# APRS_Interface.net
KiCad netlist of a schematic drawn in EAGLE
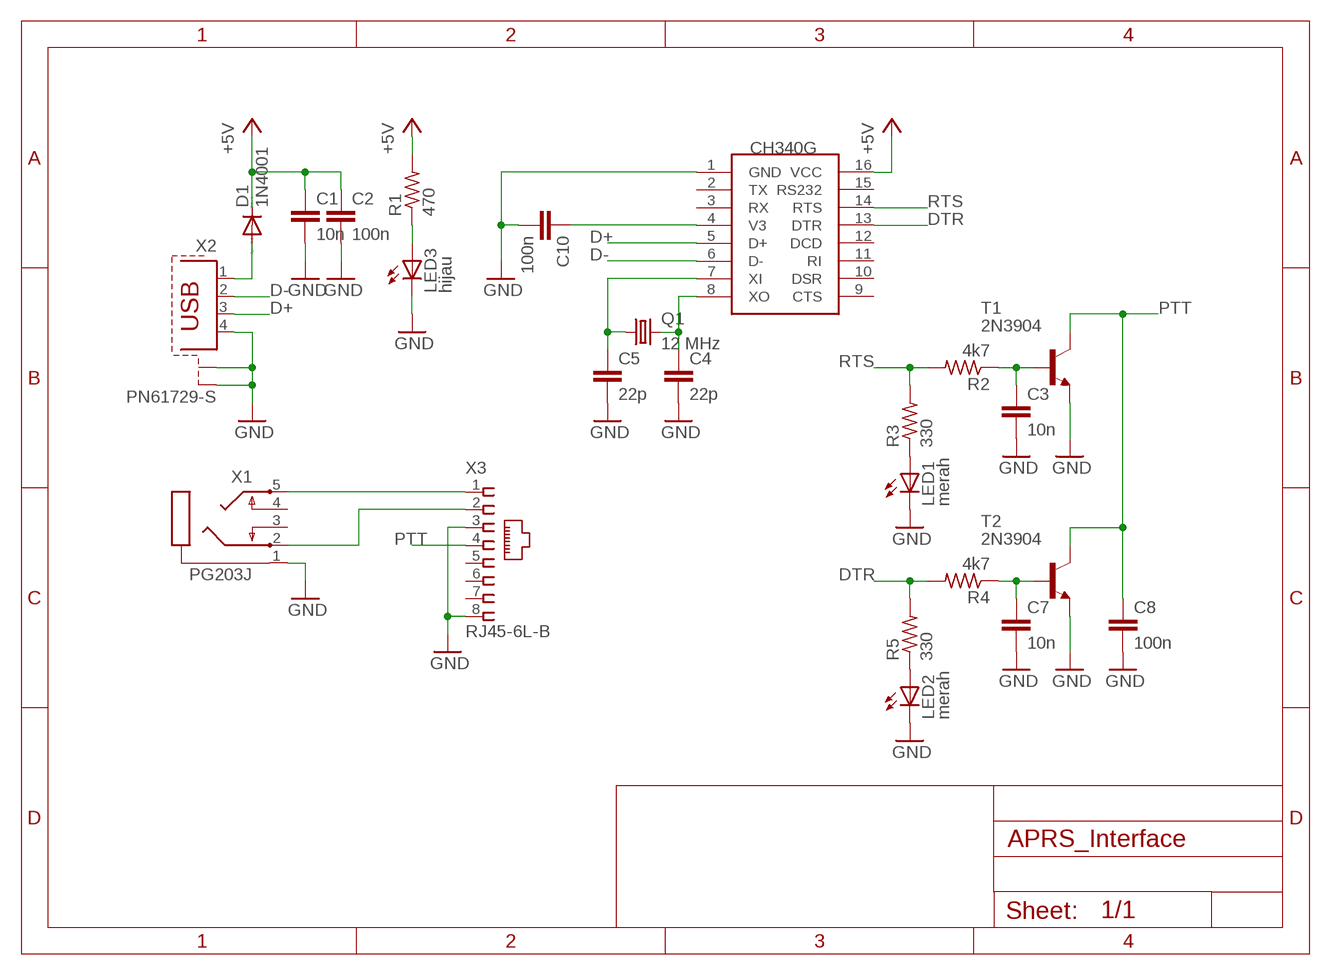
[diagram p0: schematic, sheet 1]

(export (version "E")
  (design (tool "Eeschema 10.0.6"))
  (components
    (comp (ref "C1")
      (value "10n")
      (footprint "eagle-import:C0805K")
      (libsource (lib "eagle-import") (part "C-EUC0805K"))
    )
    (comp (ref "C2")
      (value "100n")
      (footprint "eagle-import:C0805K")
      (libsource (lib "eagle-import") (part "C-EUC0805K"))
    )
    (comp (ref "C3")
      (value "10n")
      (footprint "eagle-import:C0805K")
      (libsource (lib "eagle-import") (part "C-EUC0805K"))
    )
    (comp (ref "C4")
      (value "22p")
      (footprint "eagle-import:C0805K")
      (libsource (lib "eagle-import") (part "C-EUC0805K"))
    )
    (comp (ref "C5")
      (value "22p")
      (footprint "eagle-import:C0805K")
      (libsource (lib "eagle-import") (part "C-EUC0805K"))
    )
    (comp (ref "C7")
      (value "10n")
      (footprint "eagle-import:C0805K")
      (libsource (lib "eagle-import") (part "C-EUC0805K"))
    )
    (comp (ref "C8")
      (value "100n")
      (footprint "eagle-import:C0805K")
      (libsource (lib "eagle-import") (part "C-EUC0805K"))
    )
    (comp (ref "C10")
      (value "100n")
      (footprint "eagle-import:C0805K")
      (libsource (lib "eagle-import") (part "C-EUC0805K"))
    )
    (comp (ref "D1")
      (value "1N4001")
      (footprint "eagle-import:DO35-7")
      (libsource (lib "eagle-import") (part "1N4148DO35-7"))
    )
    (comp (ref "LED1")
      (value "merah")
      (footprint "eagle-import:LED3MM")
      (libsource (lib "eagle-import") (part "LED3MM"))
    )
    (comp (ref "LED2")
      (value "merah")
      (footprint "eagle-import:LED3MM")
      (libsource (lib "eagle-import") (part "LED3MM"))
    )
    (comp (ref "LED3")
      (value "hijau")
      (footprint "eagle-import:LED3MM")
      (libsource (lib "eagle-import") (part "LED3MM"))
    )
    (comp (ref "Q1")
      (value "12 MHz")
      (footprint "eagle-import:HC49_S")
      (libsource (lib "eagle-import") (part "CRYSTALHC49S"))
    )
    (comp (ref "R1")
      (value "470")
      (footprint "eagle-import:R0805")
      (libsource (lib "eagle-import") (part "R-US_R0805"))
    )
    (comp (ref "R2")
      (value "4k7")
      (footprint "eagle-import:R0805")
      (libsource (lib "eagle-import") (part "R-US_R0805"))
    )
    (comp (ref "R3")
      (value "330")
      (footprint "eagle-import:R0805")
      (libsource (lib "eagle-import") (part "R-US_R0805"))
    )
    (comp (ref "R4")
      (value "4k7")
      (footprint "eagle-import:R0805")
      (libsource (lib "eagle-import") (part "R-US_R0805"))
    )
    (comp (ref "R5")
      (value "330")
      (footprint "eagle-import:R0805")
      (libsource (lib "eagle-import") (part "R-US_R0805"))
    )
    (comp (ref "T1")
      (value "2N3904")
      (footprint "eagle-import:TO92-EBC")
      (libsource (lib "eagle-import") (part "-NPN-TO92-EBC2N3904"))
    )
    (comp (ref "T2")
      (value "2N3904")
      (footprint "eagle-import:TO92-EBC")
      (libsource (lib "eagle-import") (part "-NPN-TO92-EBC2N3904"))
    )
    (comp (ref "U$1")
      (value "CH340G")
      (footprint "eagle-import:SOIC16")
      (libsource (lib "eagle-import") (part "CH340G"))
    )
    (comp (ref "X1")
      (value "PG203J")
      (footprint "eagle-import:PG203J")
      (libsource (lib "eagle-import") (part "PG203J"))
    )
    (comp (ref "X2")
      (value "PN61729-S")
      (footprint "eagle-import:PN61729-S")
      (libsource (lib "eagle-import") (part "PN61729-S"))
    )
    (comp (ref "X3")
      (value "RJ45-6L-B")
      (footprint "eagle-import:RJ45-NO-SHIELD")
      (libsource (lib "eagle-import") (part "RJ45-6L-B"))
    )
  )
  (nets
    (net (code "1") (name "+5V") (class "Default")
      (node (ref "C1") (pin "1") (pinfunction "1_1") (pintype "passive"))
      (node (ref "C2") (pin "1") (pinfunction "1_1") (pintype "passive"))
      (node (ref "D1") (pin "C") (pinfunction "C_C") (pintype "passive"))
      (node (ref "R1") (pin "2") (pinfunction "2_2") (pintype "passive"))
      (node (ref "U$1") (pin "16") (pinfunction "VCC_16") (pintype "bidirectional"))
    )
    (net (code "2") (name "/D+") (class "Default")
      (node (ref "U$1") (pin "5") (pinfunction "D+_5") (pintype "bidirectional"))
      (node (ref "X2") (pin "3") (pinfunction "3_3") (pintype "passive"))
    )
    (net (code "3") (name "/D-") (class "Default")
      (node (ref "U$1") (pin "6") (pinfunction "D-_6") (pintype "bidirectional"))
      (node (ref "X2") (pin "2") (pinfunction "2_2") (pintype "passive"))
    )
    (net (code "4") (name "/DTR") (class "Default")
      (node (ref "R4") (pin "2") (pinfunction "2_2") (pintype "passive"))
      (node (ref "R5") (pin "2") (pinfunction "2_2") (pintype "passive"))
      (node (ref "U$1") (pin "13") (pinfunction "DTR_13") (pintype "bidirectional"))
    )
    (net (code "5") (name "/PTT") (class "Default")
      (node (ref "C8") (pin "1") (pinfunction "1_1") (pintype "passive"))
      (node (ref "T1") (pin "C") (pinfunction "C_C") (pintype "passive"))
      (node (ref "T2") (pin "C") (pinfunction "C_C") (pintype "passive"))
      (node (ref "X3") (pin "4") (pinfunction "4_4") (pintype "passive"))
    )
    (net (code "6") (name "/RTS") (class "Default")
      (node (ref "R2") (pin "2") (pinfunction "2_2") (pintype "passive"))
      (node (ref "R3") (pin "2") (pinfunction "2_2") (pintype "passive"))
      (node (ref "U$1") (pin "14") (pinfunction "RTS_14") (pintype "bidirectional"))
    )
    (net (code "7") (name "GND") (class "Default")
      (node (ref "C1") (pin "2") (pinfunction "2_2") (pintype "passive"))
      (node (ref "C10") (pin "2") (pinfunction "2_2") (pintype "passive"))
      (node (ref "C2") (pin "2") (pinfunction "2_2") (pintype "passive"))
      (node (ref "C3") (pin "2") (pinfunction "2_2") (pintype "passive"))
      (node (ref "C4") (pin "2") (pinfunction "2_2") (pintype "passive"))
      (node (ref "C5") (pin "2") (pinfunction "2_2") (pintype "passive"))
      (node (ref "C7") (pin "2") (pinfunction "2_2") (pintype "passive"))
      (node (ref "C8") (pin "2") (pinfunction "2_2") (pintype "passive"))
      (node (ref "LED1") (pin "K") (pinfunction "C_K") (pintype "passive"))
      (node (ref "LED2") (pin "K") (pinfunction "C_K") (pintype "passive"))
      (node (ref "LED3") (pin "K") (pinfunction "C_K") (pintype "passive"))
      (node (ref "T1") (pin "E") (pinfunction "E_E") (pintype "passive"))
      (node (ref "T2") (pin "E") (pinfunction "E_E") (pintype "passive"))
      (node (ref "U$1") (pin "1") (pinfunction "GND_1") (pintype "bidirectional"))
      (node (ref "X1") (pin "1") (pinfunction "1_1") (pintype "passive"))
      (node (ref "X2") (pin "4") (pinfunction "4_4") (pintype "passive"))
      (node (ref "X2") (pin "S1") (pinfunction "S1_S1") (pintype "passive"))
      (node (ref "X2") (pin "S2") (pinfunction "S2_S2") (pintype "passive"))
      (node (ref "X3") (pin "3") (pinfunction "3_3") (pintype "passive"))
      (node (ref "X3") (pin "8") (pinfunction "8_8") (pintype "passive"))
    )
    (net (code "8") (name "Net-(C3-Pad1)") (class "Default")
      (node (ref "C3") (pin "1") (pinfunction "1_1") (pintype "passive"))
      (node (ref "R2") (pin "1") (pinfunction "1_1") (pintype "passive"))
      (node (ref "T1") (pin "B") (pinfunction "B_B") (pintype "passive"))
    )
    (net (code "9") (name "Net-(C7-Pad1)") (class "Default")
      (node (ref "C7") (pin "1") (pinfunction "1_1") (pintype "passive"))
      (node (ref "R4") (pin "1") (pinfunction "1_1") (pintype "passive"))
      (node (ref "T2") (pin "B") (pinfunction "B_B") (pintype "passive"))
    )
    (net (code "10") (name "Net-(D1-PadA)") (class "Default")
      (node (ref "D1") (pin "A") (pinfunction "A_A") (pintype "passive"))
      (node (ref "X2") (pin "1") (pinfunction "1_1") (pintype "passive"))
    )
    (net (code "11") (name "Net-(LED1-PadA)") (class "Default")
      (node (ref "LED1") (pin "A") (pinfunction "A_A") (pintype "passive"))
      (node (ref "R3") (pin "1") (pinfunction "1_1") (pintype "passive"))
    )
    (net (code "12") (name "Net-(LED2-PadA)") (class "Default")
      (node (ref "LED2") (pin "A") (pinfunction "A_A") (pintype "passive"))
      (node (ref "R5") (pin "1") (pinfunction "1_1") (pintype "passive"))
    )
    (net (code "13") (name "Net-(LED3-PadA)") (class "Default")
      (node (ref "LED3") (pin "A") (pinfunction "A_A") (pintype "passive"))
      (node (ref "R1") (pin "1") (pinfunction "1_1") (pintype "passive"))
    )
    (net (code "14") (name "Net-(U$1-V3)") (class "Default")
      (node (ref "C10") (pin "1") (pinfunction "1_1") (pintype "passive"))
      (node (ref "U$1") (pin "4") (pinfunction "V3_4") (pintype "bidirectional"))
    )
    (net (code "15") (name "Net-(U$1-XI)") (class "Default")
      (node (ref "C5") (pin "1") (pinfunction "1_1") (pintype "passive"))
      (node (ref "Q1") (pin "1") (pinfunction "1_1") (pintype "passive"))
      (node (ref "U$1") (pin "7") (pinfunction "XI_7") (pintype "bidirectional"))
    )
    (net (code "16") (name "Net-(U$1-XO)") (class "Default")
      (node (ref "C4") (pin "1") (pinfunction "1_1") (pintype "passive"))
      (node (ref "Q1") (pin "2") (pinfunction "2_2") (pintype "passive"))
      (node (ref "U$1") (pin "8") (pinfunction "XO_8") (pintype "bidirectional"))
    )
    (net (code "17") (name "Net-(X1-Pad2)") (class "Default")
      (node (ref "X1") (pin "2") (pinfunction "2_2") (pintype "passive"))
      (node (ref "X3") (pin "2") (pinfunction "2_2") (pintype "passive"))
    )
    (net (code "18") (name "Net-(X1-Pad5)") (class "Default")
      (node (ref "X1") (pin "5") (pinfunction "5_5") (pintype "passive"))
      (node (ref "X3") (pin "1") (pinfunction "1_1") (pintype "passive"))
    )
    (net (code "19") (name "unconnected-(U$1-CTS-Pad9)") (class "Default")
      (node (ref "U$1") (pin "9") (pinfunction "CTS_9") (pintype "bidirectional"))
    )
    (net (code "20") (name "unconnected-(U$1-DCD-Pad12)") (class "Default")
      (node (ref "U$1") (pin "12") (pinfunction "DCD_12") (pintype "bidirectional"))
    )
    (net (code "21") (name "unconnected-(U$1-DSR-Pad10)") (class "Default")
      (node (ref "U$1") (pin "10") (pinfunction "DSR_10") (pintype "bidirectional"))
    )
    (net (code "22") (name "unconnected-(U$1-RI-Pad11)") (class "Default")
      (node (ref "U$1") (pin "11") (pinfunction "RI_11") (pintype "bidirectional"))
    )
    (net (code "23") (name "unconnected-(U$1-RS232-Pad15)") (class "Default")
      (node (ref "U$1") (pin "15") (pinfunction "RS232_15") (pintype "bidirectional"))
    )
    (net (code "24") (name "unconnected-(U$1-RX-Pad3)") (class "Default")
      (node (ref "U$1") (pin "3") (pinfunction "RX_3") (pintype "bidirectional"))
    )
    (net (code "25") (name "unconnected-(U$1-TX-Pad2)") (class "Default")
      (node (ref "U$1") (pin "2") (pinfunction "TX_2") (pintype "bidirectional"))
    )
    (net (code "26") (name "unconnected-(X1-Pad3)") (class "Default")
      (node (ref "X1") (pin "3") (pinfunction "3_3") (pintype "passive"))
    )
    (net (code "27") (name "unconnected-(X1-Pad4)") (class "Default")
      (node (ref "X1") (pin "4") (pinfunction "4_4") (pintype "passive"))
    )
    (net (code "28") (name "unconnected-(X3-Pad5)") (class "Default")
      (node (ref "X3") (pin "5") (pinfunction "5_5") (pintype "passive"))
    )
    (net (code "29") (name "unconnected-(X3-Pad6)") (class "Default")
      (node (ref "X3") (pin "6") (pinfunction "6_6") (pintype "passive"))
    )
    (net (code "30") (name "unconnected-(X3-Pad7)") (class "Default")
      (node (ref "X3") (pin "7") (pinfunction "7_7") (pintype "passive"))
    )
  )
)
